# ATtiny_4585_dev_board_with_power.net
KiCad netlist of a schematic drawn in EAGLE
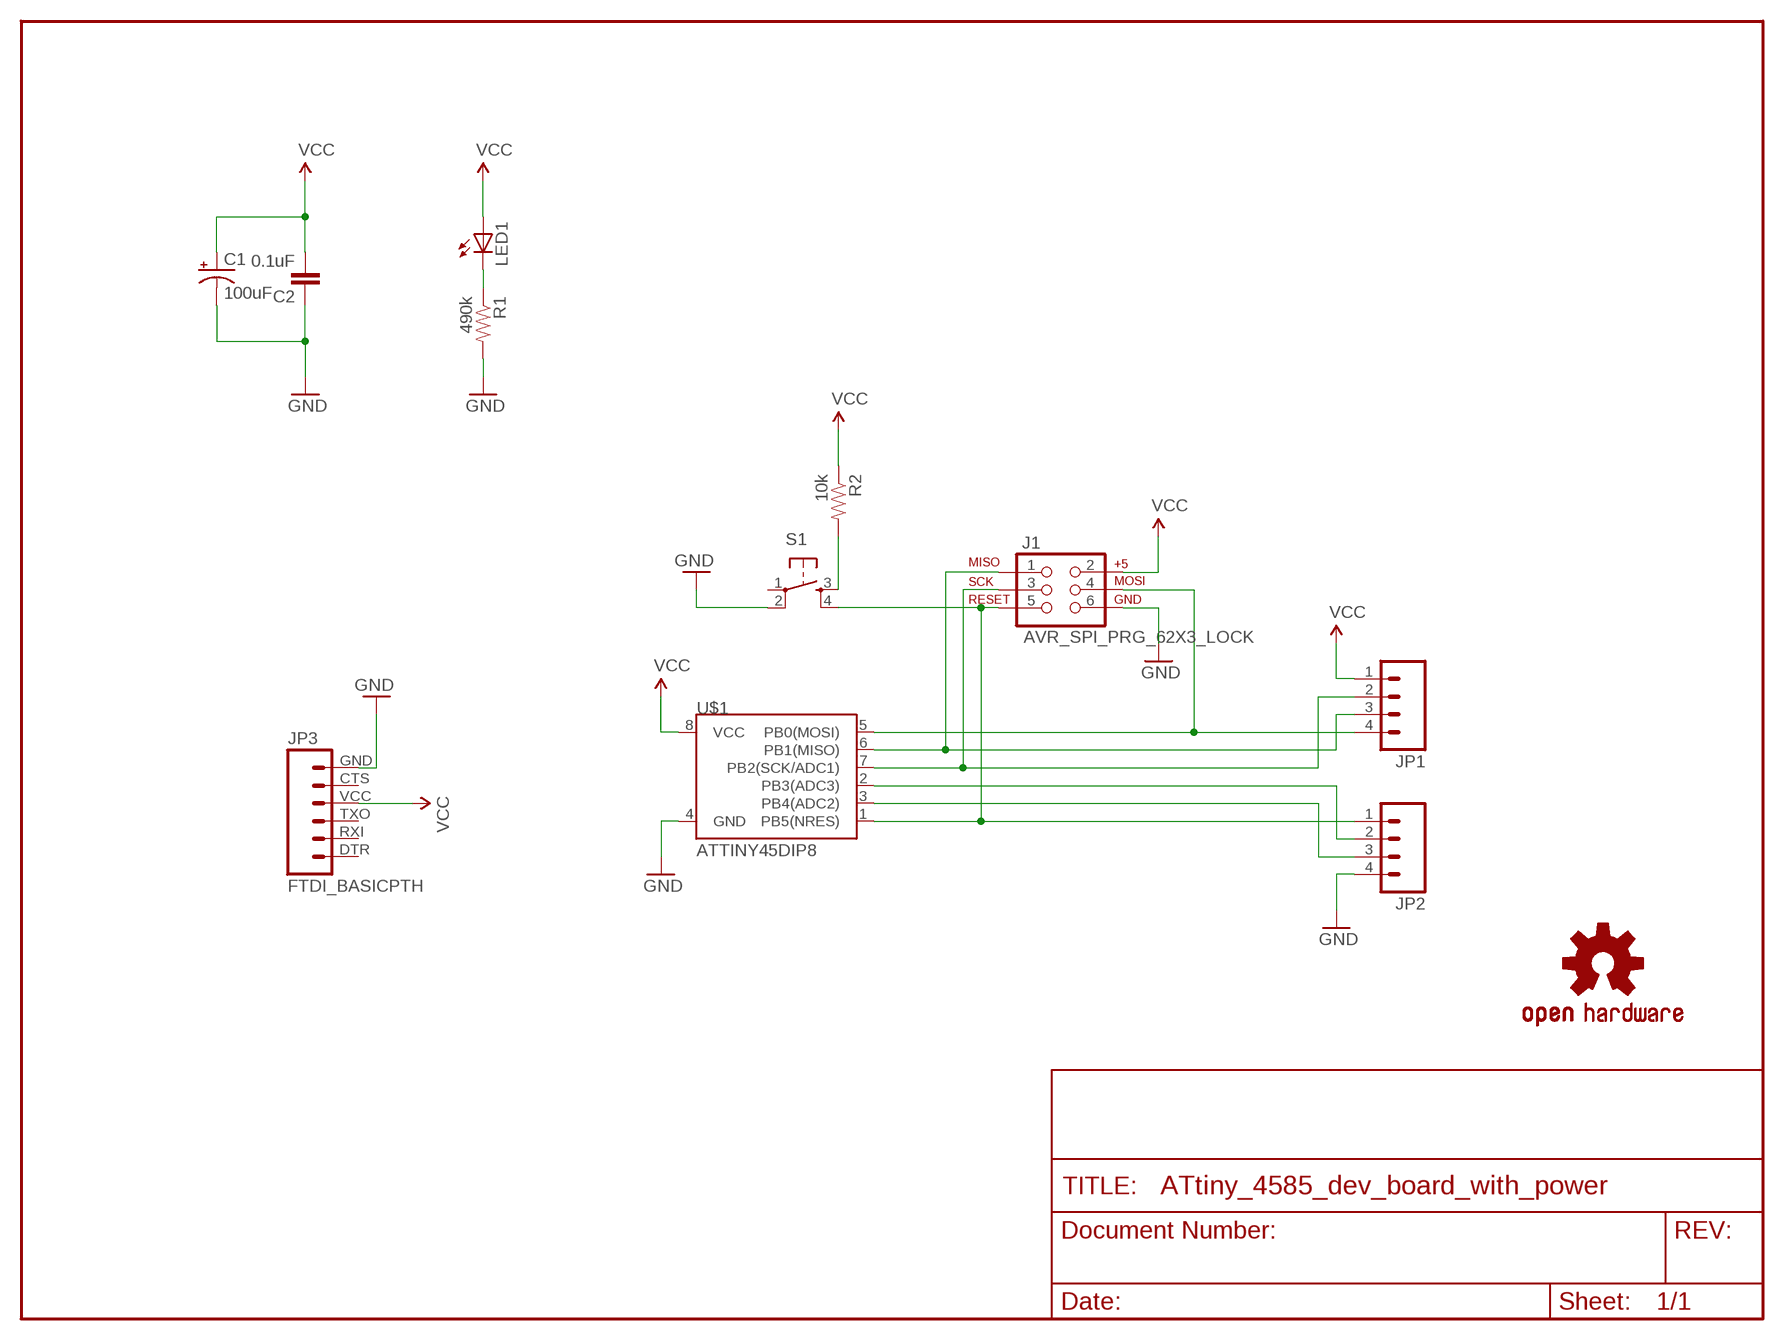
[diagram p0: schematic, sheet 1]

(export (version "E")
  (design (tool "Eeschema 10.0.6"))
  (components
    (comp (ref "C1")
      (value "100uF")
      (footprint "eagle-import:CPOL-RADIAL-100UF-25V")
      (libsource (lib "eagle-import") (part "CAP_POLPTH1"))
    )
    (comp (ref "C2")
      (value "0.1uF")
      (footprint "eagle-import:CAP-PTH-5MM")
      (libsource (lib "eagle-import") (part "CAPPTH1"))
    )
    (comp (ref "J1")
      (value "AVR_SPI_PRG_62X3_LOCK")
      (footprint "eagle-import:2X3_LOCK")
      (libsource (lib "eagle-import") (part "AVR_SPI_PRG_62X3_LOCK"))
    )
    (comp (ref "JP1")
      (value "M04LOCK")
      (footprint "eagle-import:1X04_LOCK")
      (libsource (lib "eagle-import") (part "M04LOCK"))
    )
    (comp (ref "JP2")
      (value "M04LOCK")
      (footprint "eagle-import:1X04_LOCK")
      (libsource (lib "eagle-import") (part "M04LOCK"))
    )
    (comp (ref "JP3")
      (value "FTDI_BASICPTH")
      (footprint "eagle-import:FTDI_BASIC")
      (libsource (lib "eagle-import") (part "FTDI_BASICPTH"))
    )
    (comp (ref "LED1")
      (value "LED5MM")
      (footprint "eagle-import:LED5MM")
      (libsource (lib "eagle-import") (part "LED5MM"))
    )
    (comp (ref "R1")
      (value "490k")
      (footprint "eagle-import:AXIAL-0.4")
      (libsource (lib "eagle-import") (part "RESISTORPTH-1/4W"))
    )
    (comp (ref "R2")
      (value "10k")
      (footprint "eagle-import:AXIAL-0.4")
      (libsource (lib "eagle-import") (part "RESISTORPTH-1/4W"))
    )
    (comp (ref "S1")
      (value "TAC_SWITCHPTH")
      (footprint "eagle-import:TACTILE-PTH")
      (libsource (lib "eagle-import") (part "TAC_SWITCHPTH"))
    )
    (comp (ref "U$1")
      (value "ATTINY45DIP8")
      (footprint "eagle-import:DIP08")
      (libsource (lib "eagle-import") (part "ATTINY45DIP8"))
    )
    (comp (ref "U$2")
      (value "OSHW-LOGOS")
      (footprint "eagle-import:OSHW-LOGO-S")
      (libsource (lib "eagle-import") (part "OSHW-LOGOS"))
    )
  )
  (nets
    (net (code "1") (name "GND") (class "Default")
      (node (ref "C1") (pin "2") (pinfunction "-_2") (pintype "passive"))
      (node (ref "C2") (pin "1") (pinfunction "1_1") (pintype "passive"))
      (node (ref "J1") (pin "6") (pinfunction "6_6") (pintype "passive"))
      (node (ref "JP2") (pin "4") (pinfunction "4_4") (pintype "passive"))
      (node (ref "JP3") (pin "GND") (pinfunction "6_GND") (pintype "passive"))
      (node (ref "R1") (pin "P$2") (pinfunction "2_P$2") (pintype "passive"))
      (node (ref "S1") (pin "2") (pinfunction "2_2") (pintype "passive"))
      (node (ref "U$1") (pin "4") (pinfunction "GND_4") (pintype "bidirectional"))
    )
    (net (code "2") (name "Net-(LED1-C)") (class "Default")
      (node (ref "LED1") (pin "K") (pinfunction "C_K") (pintype "passive"))
      (node (ref "R1") (pin "P$1") (pinfunction "1_P$1") (pintype "passive"))
    )
    (net (code "3") (name "Net-(R2-2)") (class "Default")
      (node (ref "R2") (pin "P$2") (pinfunction "2_P$2") (pintype "passive"))
      (node (ref "S1") (pin "3") (pinfunction "3_3") (pintype "passive"))
    )
    (net (code "4") (name "Net-(U$1-PB0(MOSI))") (class "Default")
      (node (ref "J1") (pin "4") (pinfunction "4_4") (pintype "passive"))
      (node (ref "JP1") (pin "4") (pinfunction "4_4") (pintype "passive"))
      (node (ref "U$1") (pin "5") (pinfunction "PB0(MOSI)_5") (pintype "bidirectional"))
    )
    (net (code "5") (name "Net-(U$1-PB1(MISO))") (class "Default")
      (node (ref "J1") (pin "1") (pinfunction "1_1") (pintype "passive"))
      (node (ref "JP1") (pin "3") (pinfunction "3_3") (pintype "passive"))
      (node (ref "U$1") (pin "6") (pinfunction "PB1(MISO)_6") (pintype "bidirectional"))
    )
    (net (code "6") (name "Net-(U$1-PB2(SCK{slash}ADC1))") (class "Default")
      (node (ref "J1") (pin "3") (pinfunction "3_3") (pintype "passive"))
      (node (ref "JP1") (pin "2") (pinfunction "2_2") (pintype "passive"))
      (node (ref "U$1") (pin "7") (pinfunction "PB2(SCK/ADC1)_7") (pintype "bidirectional"))
    )
    (net (code "7") (name "Net-(U$1-PB3(ADC3))") (class "Default")
      (node (ref "JP2") (pin "2") (pinfunction "2_2") (pintype "passive"))
      (node (ref "U$1") (pin "2") (pinfunction "PB3(ADC3)_2") (pintype "bidirectional"))
    )
    (net (code "8") (name "Net-(U$1-PB4(ADC2))") (class "Default")
      (node (ref "JP2") (pin "3") (pinfunction "3_3") (pintype "passive"))
      (node (ref "U$1") (pin "3") (pinfunction "PB4(ADC2)_3") (pintype "bidirectional"))
    )
    (net (code "9") (name "Net-(U$1-PB5(NRES))") (class "Default")
      (node (ref "J1") (pin "5") (pinfunction "5_5") (pintype "passive"))
      (node (ref "JP2") (pin "1") (pinfunction "1_1") (pintype "passive"))
      (node (ref "S1") (pin "4") (pinfunction "4_4") (pintype "passive"))
      (node (ref "U$1") (pin "1") (pinfunction "PB5(NRES)_1") (pintype "bidirectional"))
    )
    (net (code "10") (name "VCC") (class "Default")
      (node (ref "C1") (pin "1") (pinfunction "+_1") (pintype "passive"))
      (node (ref "C2") (pin "2") (pinfunction "2_2") (pintype "passive"))
      (node (ref "J1") (pin "2") (pinfunction "2_2") (pintype "passive"))
      (node (ref "JP1") (pin "1") (pinfunction "1_1") (pintype "passive"))
      (node (ref "JP3") (pin "VCC") (pinfunction "4_VCC") (pintype "passive"))
      (node (ref "LED1") (pin "A") (pinfunction "A_A") (pintype "passive"))
      (node (ref "R2") (pin "P$1") (pinfunction "1_P$1") (pintype "passive"))
      (node (ref "U$1") (pin "8") (pinfunction "VCC_8") (pintype "bidirectional"))
    )
    (net (code "11") (name "unconnected-(JP3-1-PadDTR)") (class "Default")
      (node (ref "JP3") (pin "DTR") (pinfunction "1_DTR") (pintype "passive"))
    )
    (net (code "12") (name "unconnected-(JP3-2-PadRXI)") (class "Default")
      (node (ref "JP3") (pin "RXI") (pinfunction "2_RXI") (pintype "passive"))
    )
    (net (code "13") (name "unconnected-(JP3-3-PadTXO)") (class "Default")
      (node (ref "JP3") (pin "TXO") (pinfunction "3_TXO") (pintype "passive"))
    )
    (net (code "14") (name "unconnected-(JP3-5-PadCTS)") (class "Default")
      (node (ref "JP3") (pin "CTS") (pinfunction "5_CTS") (pintype "passive"))
    )
    (net (code "15") (name "unconnected-(S1-Pad1)") (class "Default")
      (node (ref "S1") (pin "1") (pinfunction "1_1") (pintype "passive"))
    )
  )
)
